# OpenBook.net
KiCad netlist of a schematic drawn in EAGLE
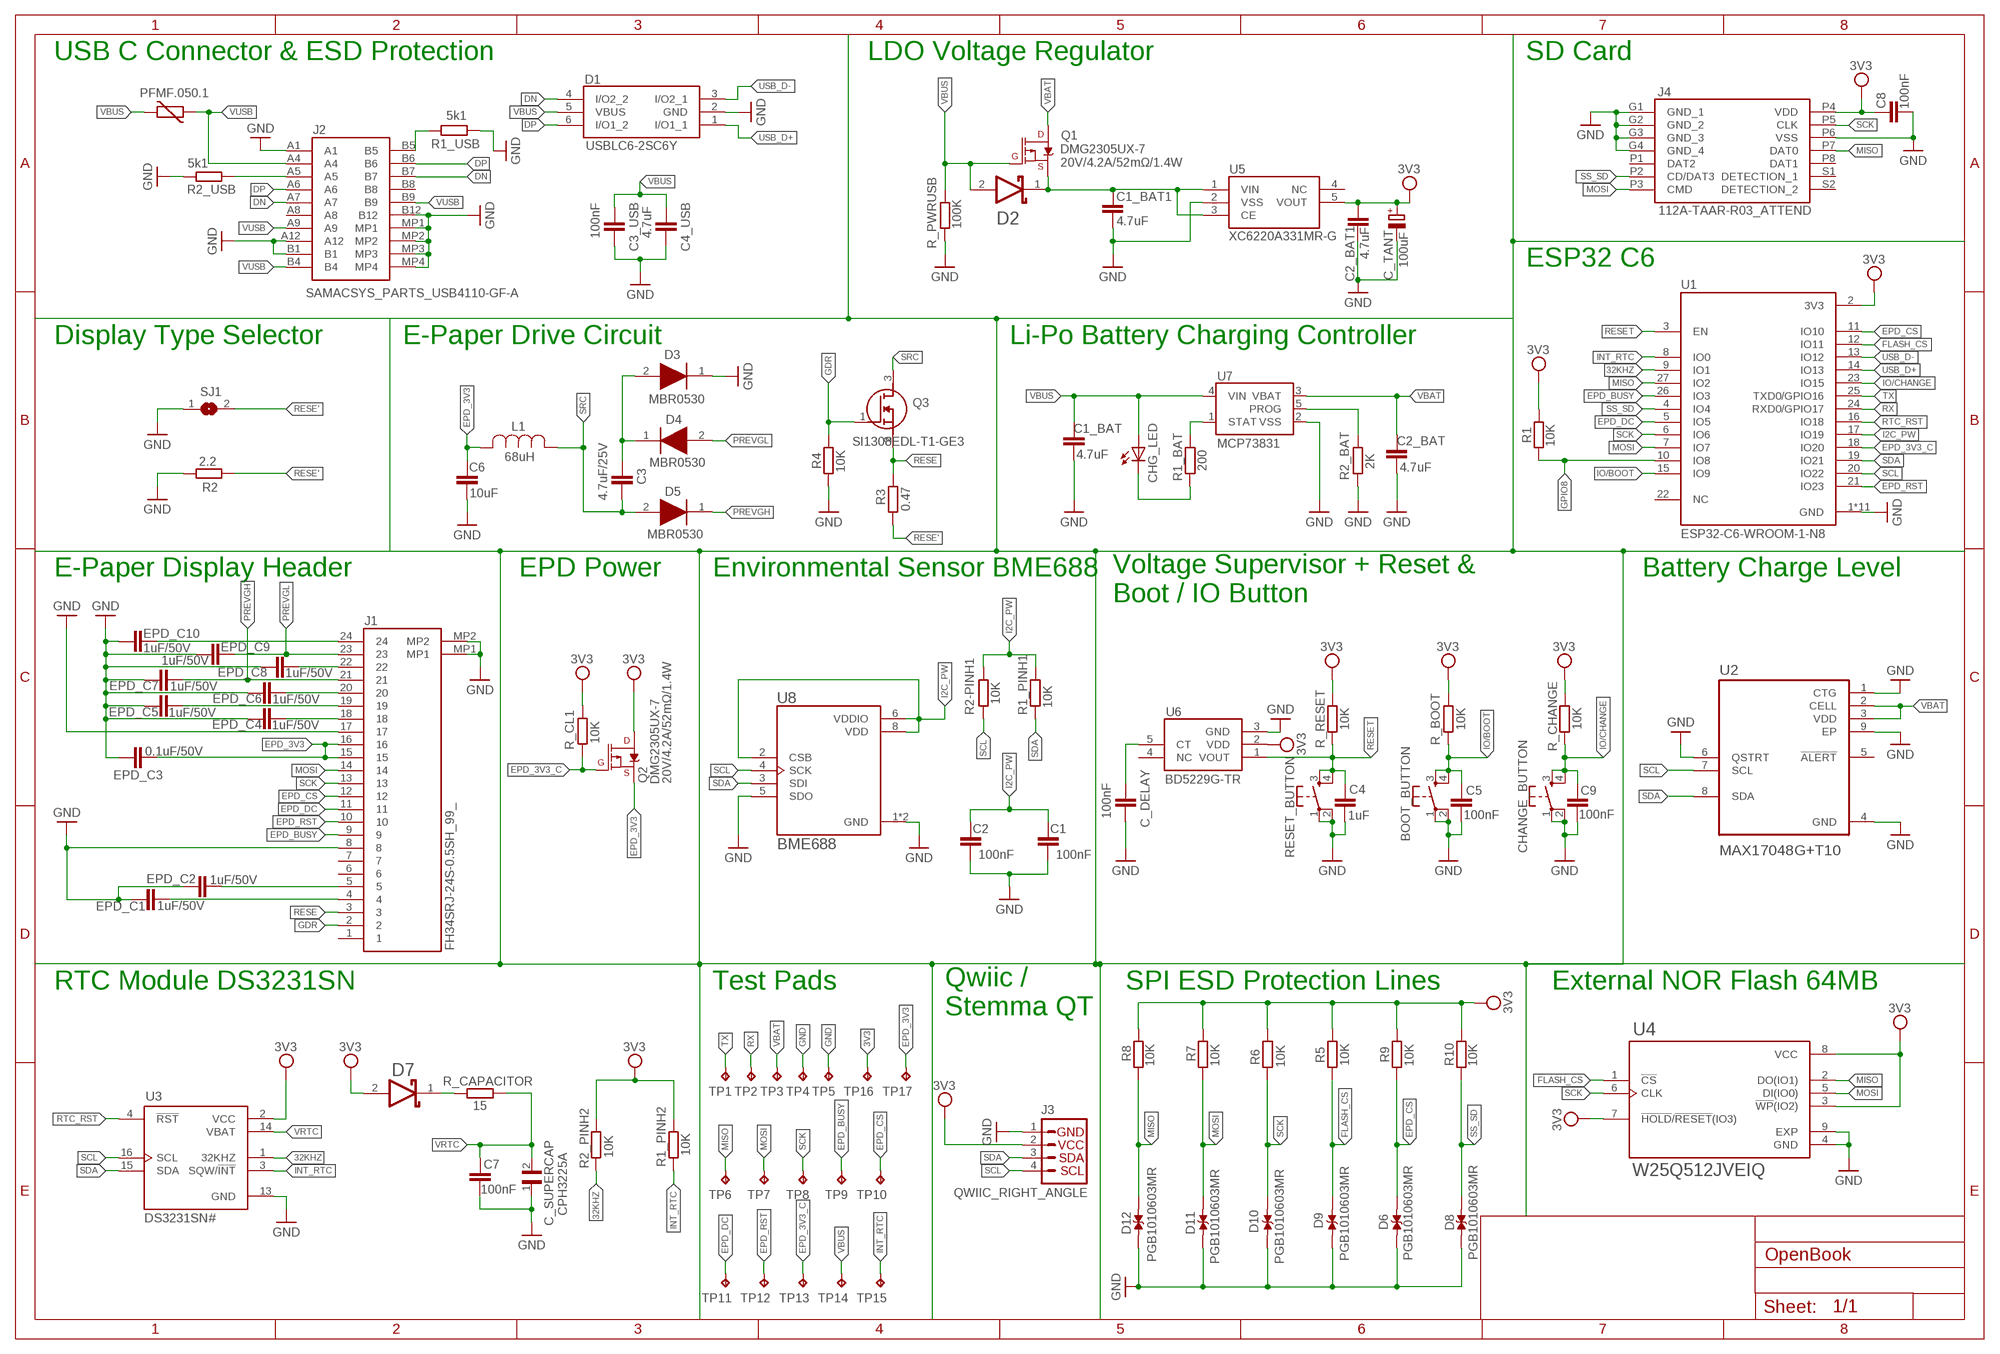
[diagram p0: schematic, sheet 1]

(export (version "E")
  (design (tool "Eeschema 10.0.6"))
  (components
    (comp (ref "BOOT_BUTTON")
      (value "BUTTON_CUSYOMV1")
      (footprint "eagle-import:MYBUTTON")
      (libsource (lib "eagle-import") (part "BUTTON_CUSYOMV1"))
    )
    (comp (ref "C1")
      (value "100nF")
      (footprint "eagle-import:EAGLE-LTSPICE_C0402")
      (libsource (lib "eagle-import") (part "ESP32_WROVER_EAGLE-LTSPICE_C0402"))
    )
    (comp (ref "C1_BAT")
      (value "4.7uF")
      (footprint "eagle-import:EAGLE-LTSPICE_C0402")
      (libsource (lib "eagle-import") (part "ESP32_WROVER_EAGLE-LTSPICE_C0402"))
    )
    (comp (ref "C1_BAT1")
      (value "4.7uF")
      (footprint "eagle-import:EAGLE-LTSPICE_C0402")
      (libsource (lib "eagle-import") (part "ESP32_WROVER_EAGLE-LTSPICE_C0402"))
    )
    (comp (ref "C2")
      (value "100nF")
      (footprint "eagle-import:EAGLE-LTSPICE_C0402")
      (libsource (lib "eagle-import") (part "ESP32_WROVER_EAGLE-LTSPICE_C0402"))
    )
    (comp (ref "C2_BAT")
      (value "4.7uF")
      (footprint "eagle-import:EAGLE-LTSPICE_C0402")
      (libsource (lib "eagle-import") (part "ESP32_WROVER_EAGLE-LTSPICE_C0402"))
    )
    (comp (ref "C2_BAT1")
      (value "4.7uF")
      (footprint "eagle-import:EAGLE-LTSPICE_C0402")
      (libsource (lib "eagle-import") (part "ESP32_WROVER_EAGLE-LTSPICE_C0402"))
    )
    (comp (ref "C3")
      (value "4.7uF/25V")
      (footprint "eagle-import:EAGLE-LTSPICE_C0402")
      (libsource (lib "eagle-import") (part "ESP32_WROVER_EAGLE-LTSPICE_C0402"))
    )
    (comp (ref "C3_USB")
      (value "100nF")
      (footprint "eagle-import:EAGLE-LTSPICE_C0402")
      (libsource (lib "eagle-import") (part "ESP32_WROVER_EAGLE-LTSPICE_C0402"))
    )
    (comp (ref "C4")
      (value "1uF")
      (footprint "eagle-import:EAGLE-LTSPICE_C0402")
      (libsource (lib "eagle-import") (part "ESP32_WROVER_EAGLE-LTSPICE_C0402"))
    )
    (comp (ref "C4_USB")
      (value "4.7uF")
      (footprint "eagle-import:EAGLE-LTSPICE_C0402")
      (libsource (lib "eagle-import") (part "ESP32_WROVER_EAGLE-LTSPICE_C0402"))
    )
    (comp (ref "C5")
      (value "100nF")
      (footprint "eagle-import:EAGLE-LTSPICE_C0402")
      (libsource (lib "eagle-import") (part "ESP32_WROVER_EAGLE-LTSPICE_C0402"))
    )
    (comp (ref "C6")
      (value "10uF")
      (footprint "eagle-import:EAGLE-LTSPICE_C0402")
      (libsource (lib "eagle-import") (part "ESP32_WROVER_EAGLE-LTSPICE_C0402"))
    )
    (comp (ref "C7")
      (value "100nF")
      (footprint "eagle-import:EAGLE-LTSPICE_C0402")
      (libsource (lib "eagle-import") (part "ESP32_WROVER_EAGLE-LTSPICE_C0402"))
    )
    (comp (ref "C8")
      (value "100nF")
      (footprint "eagle-import:EAGLE-LTSPICE_C0402")
      (libsource (lib "eagle-import") (part "ESP32_WROVER_EAGLE-LTSPICE_C0402"))
    )
    (comp (ref "C9")
      (value "100nF")
      (footprint "eagle-import:EAGLE-LTSPICE_C0402")
      (libsource (lib "eagle-import") (part "ESP32_WROVER_EAGLE-LTSPICE_C0402"))
    )
    (comp (ref "CHANGE_BUTTON")
      (value "BUTTON_CUSYOMV1")
      (footprint "eagle-import:MYBUTTON")
      (libsource (lib "eagle-import") (part "BUTTON_CUSYOMV1"))
    )
    (comp (ref "CHG_LED")
      (value "ADAFRUIT_LEDCHIP-LED0603")
      (footprint "eagle-import:ADAFRUIT_CHIP-LED0603")
      (libsource (lib "eagle-import") (part "ADAFRUIT_LEDCHIP-LED0603"))
    )
    (comp (ref "C_DELAY")
      (value "100nF")
      (footprint "eagle-import:EAGLE-LTSPICE_C0402")
      (libsource (lib "eagle-import") (part "ESP32_WROVER_EAGLE-LTSPICE_C0402"))
    )
    (comp (ref "C_SUPERCAP")
      (value "CPH3225A")
      (footprint "eagle-import:CAPCP3225X100N")
      (libsource (lib "eagle-import") (part "CPH3225A"))
    )
    (comp (ref "C_TANT")
      (value "100uF")
      (footprint "eagle-import:RCL_CT3528")
      (libsource (lib "eagle-import") (part "RCL_CPOL-EUCT3528"))
    )
    (comp (ref "D1")
      (value "USBLC6-2SC6Y")
      (footprint "eagle-import:SON50P200X200X80-9N")
      (fields (field (name "MF") "STMicroelectronics") (field (name "FF") "FF"))
      (libsource (lib "eagle-import") (part "USBLC6-2SC6Y"))
    )
    (comp (ref "D2")
      (value "ESP32_WROVER_AVX---SD0805S020S1R0_AVX_SD0805S020S1R0_0_0AVX_SD0805S020S1R0_0_0")
      (footprint "eagle-import:ESP32_WROVER_AVX---SD0805S020S1R0_AVX_SD0805S020S1R0_0")
      (libsource (lib "eagle-import") (part "ESP32_WROVER_AVX---SD0805S020S1R0_AVX_SD0805S020S1R0_0_0AVX_SD0805S020S1R0_0_0"))
    )
    (comp (ref "D3")
      (value "MBR0530")
      (footprint "eagle-import:SOD3716X135N")
      (fields (field (name "MF") "ON Semiconductor"))
      (libsource (lib "eagle-import") (part "MBR0530"))
    )
    (comp (ref "D4")
      (value "MBR0530")
      (footprint "eagle-import:SOD3716X135N")
      (fields (field (name "MF") "ON Semiconductor"))
      (libsource (lib "eagle-import") (part "MBR0530"))
    )
    (comp (ref "D5")
      (value "MBR0530")
      (footprint "eagle-import:SOD3716X135N")
      (fields (field (name "MF") "ON Semiconductor"))
      (libsource (lib "eagle-import") (part "MBR0530"))
    )
    (comp (ref "D6")
      (value "PGB1010603MR")
      (footprint "eagle-import:DIOC1608X36N")
      (fields (field (name "MF") "Littelfuse Inc."))
      (libsource (lib "eagle-import") (part "PGB1010603MR"))
    )
    (comp (ref "D7")
      (value "ESP32_WROVER_AVX---SD0805S020S1R0_AVX_SD0805S020S1R0_0_0AVX_SD0805S020S1R0_0_0")
      (footprint "eagle-import:ESP32_WROVER_AVX---SD0805S020S1R0_AVX_SD0805S020S1R0_0")
      (libsource (lib "eagle-import") (part "ESP32_WROVER_AVX---SD0805S020S1R0_AVX_SD0805S020S1R0_0_0AVX_SD0805S020S1R0_0_0"))
    )
    (comp (ref "D8")
      (value "PGB1010603MR")
      (footprint "eagle-import:DIOC1608X36N")
      (fields (field (name "MF") "Littelfuse Inc."))
      (libsource (lib "eagle-import") (part "PGB1010603MR"))
    )
    (comp (ref "D9")
      (value "PGB1010603MR")
      (footprint "eagle-import:DIOC1608X36N")
      (fields (field (name "MF") "Littelfuse Inc."))
      (libsource (lib "eagle-import") (part "PGB1010603MR"))
    )
    (comp (ref "D10")
      (value "PGB1010603MR")
      (footprint "eagle-import:DIOC1608X36N")
      (fields (field (name "MF") "Littelfuse Inc."))
      (libsource (lib "eagle-import") (part "PGB1010603MR"))
    )
    (comp (ref "D11")
      (value "PGB1010603MR")
      (footprint "eagle-import:DIOC1608X36N")
      (fields (field (name "MF") "Littelfuse Inc."))
      (libsource (lib "eagle-import") (part "PGB1010603MR"))
    )
    (comp (ref "D12")
      (value "PGB1010603MR")
      (footprint "eagle-import:DIOC1608X36N")
      (fields (field (name "MF") "Littelfuse Inc."))
      (libsource (lib "eagle-import") (part "PGB1010603MR"))
    )
    (comp (ref "EPD_C1")
      (value "1uF/50V")
      (footprint "eagle-import:EAGLE-LTSPICE_C0402")
      (libsource (lib "eagle-import") (part "ESP32_WROVER_EAGLE-LTSPICE_C0402"))
    )
    (comp (ref "EPD_C2")
      (value "1uF/50V")
      (footprint "eagle-import:EAGLE-LTSPICE_C0402")
      (libsource (lib "eagle-import") (part "ESP32_WROVER_EAGLE-LTSPICE_C0402"))
    )
    (comp (ref "EPD_C3")
      (value "0.1uF/50V")
      (footprint "eagle-import:EAGLE-LTSPICE_C0402")
      (libsource (lib "eagle-import") (part "ESP32_WROVER_EAGLE-LTSPICE_C0402"))
    )
    (comp (ref "EPD_C4")
      (value "1uF/50V")
      (footprint "eagle-import:EAGLE-LTSPICE_C0402")
      (libsource (lib "eagle-import") (part "ESP32_WROVER_EAGLE-LTSPICE_C0402"))
    )
    (comp (ref "EPD_C5")
      (value "1uF/50V")
      (footprint "eagle-import:EAGLE-LTSPICE_C0402")
      (libsource (lib "eagle-import") (part "ESP32_WROVER_EAGLE-LTSPICE_C0402"))
    )
    (comp (ref "EPD_C6")
      (value "1uF/50V")
      (footprint "eagle-import:EAGLE-LTSPICE_C0402")
      (libsource (lib "eagle-import") (part "ESP32_WROVER_EAGLE-LTSPICE_C0402"))
    )
    (comp (ref "EPD_C7")
      (value "1uF/50V")
      (footprint "eagle-import:EAGLE-LTSPICE_C0402")
      (libsource (lib "eagle-import") (part "ESP32_WROVER_EAGLE-LTSPICE_C0402"))
    )
    (comp (ref "EPD_C8")
      (value "1uF/50V")
      (footprint "eagle-import:EAGLE-LTSPICE_C0402")
      (libsource (lib "eagle-import") (part "ESP32_WROVER_EAGLE-LTSPICE_C0402"))
    )
    (comp (ref "EPD_C9")
      (value "1uF/50V")
      (footprint "eagle-import:EAGLE-LTSPICE_C0402")
      (libsource (lib "eagle-import") (part "ESP32_WROVER_EAGLE-LTSPICE_C0402"))
    )
    (comp (ref "EPD_C10")
      (value "1uF/50V")
      (footprint "eagle-import:EAGLE-LTSPICE_C0402")
      (libsource (lib "eagle-import") (part "ESP32_WROVER_EAGLE-LTSPICE_C0402"))
    )
    (comp (ref "J1")
      (value "FH34SRJ-24S-0.5SH_99_")
      (footprint "eagle-import:FH34SRJ24S05SH99")
      (fields
        (field (name "MANUFACTURER_PART_NUMBER") "FH34SRJ-24S-0.5SH(99)")
        (field (name "MOUSER_PART_NUMBER") "798-FH34SRJ24S05SH99")
      )
      (libsource (lib "eagle-import") (part "FH34SRJ-24S-0.5SH_99_"))
    )
    (comp (ref "J2")
      (value "SAMACSYS_PARTS_USB4110-GF-A")
      (footprint "eagle-import:SAMACSYS_PARTS_USB4110GFA")
      (fields
        (field (name "MANUFACTURER_PART_NUMBER") "USB4110-GF-A")
        (field (name "MOUSER_PART_NUMBER") "640-USB4110-GF-A")
      )
      (libsource (lib "eagle-import") (part "SAMACSYS_PARTS_USB4110-GF-A"))
    )
    (comp (ref "J3")
      (value "QWIIC_RIGHT_ANGLE")
      (footprint "eagle-import:JST04_1MM_RA")
      (libsource (lib "eagle-import") (part "QWIIC_CONNECTORJS-1MM"))
    )
    (comp (ref "J4")
      (value "112A-TAAR-R03_ATTEND")
      (footprint "eagle-import:112ATAARR03ATTEND")
      (libsource (lib "eagle-import") (part "112A-TAAR-R03_ATTEND"))
    )
    (comp (ref "L1")
      (value "68uH")
      (footprint "eagle-import:IND_4828-WE-TPC_WRE")
      (libsource (lib "eagle-import") (part "744043680IND_4828-WE-TPC_WRE"))
    )
    (comp (ref "PFMF.050.1")
      (value "ESP32C6_VARISTORCN1812")
      (footprint "eagle-import:ESP32C6_VARISTOR_CT_CN1812")
      (libsource (lib "eagle-import") (part "ESP32C6_VARISTORCN1812"))
    )
    (comp (ref "Q1")
      (value "20V/4.2A/52mΩ/1.4W")
      (footprint "eagle-import:ESP32_WROVER_SPARKFUN-DISCRETESEMI_SOT23-3")
      (fields (field (name "PROD_ID") "TRAN-14388") (field (name "PROD_ID_1") "DMG2305UX-7"))
      (libsource (lib "eagle-import") (part "ESP32_WROVER_SPARKFUN-DISCRETESEMI_MOSFET_PCH-DMG2305UX-7"))
    )
    (comp (ref "Q2")
      (value "20V/4.2A/52mΩ/1.4W")
      (footprint "eagle-import:ESP32_WROVER_SPARKFUN-DISCRETESEMI_SOT23-3")
      (fields (field (name "PROD_ID") "TRAN-14388") (field (name "PROD_ID_1") "DMG2305UX-7"))
      (libsource (lib "eagle-import") (part "ESP32_WROVER_SPARKFUN-DISCRETESEMI_MOSFET_PCH-DMG2305UX-7"))
    )
    (comp (ref "Q3")
      (value "SI1308EDL-T1-GE3")
      (footprint "eagle-import:SOT65P210X110-3N")
      (fields (field (name "MF") "Vishay Siliconix"))
      (libsource (lib "eagle-import") (part "SI1308EDL-T1-GE3"))
    )
    (comp (ref "R1")
      (value "10K")
      (footprint "eagle-import:ESP32_WROVER_EAGLE-LTSPICE_R0402")
      (libsource (lib "eagle-import") (part "ESP32_WROVER_EAGLE-LTSPICE_RR0402"))
    )
    (comp (ref "R1_BAT")
      (value "200")
      (footprint "eagle-import:ESP32_WROVER_EAGLE-LTSPICE_R0402")
      (libsource (lib "eagle-import") (part "ESP32_WROVER_EAGLE-LTSPICE_RR0402"))
    )
    (comp (ref "R1_PINH1")
      (value "10K")
      (footprint "eagle-import:ESP32_WROVER_EAGLE-LTSPICE_R0402")
      (libsource (lib "eagle-import") (part "ESP32_WROVER_EAGLE-LTSPICE_RR0402"))
    )
    (comp (ref "R1_PINH2")
      (value "10K")
      (footprint "eagle-import:ESP32_WROVER_EAGLE-LTSPICE_R0402")
      (libsource (lib "eagle-import") (part "ESP32_WROVER_EAGLE-LTSPICE_RR0402"))
    )
    (comp (ref "R1_USB")
      (value "5k1")
      (footprint "eagle-import:ESP32_WROVER_EAGLE-LTSPICE_R0402")
      (libsource (lib "eagle-import") (part "ESP32_WROVER_EAGLE-LTSPICE_RR0402"))
    )
    (comp (ref "R2")
      (value "2.2")
      (footprint "eagle-import:ESP32_WROVER_EAGLE-LTSPICE_R0402")
      (libsource (lib "eagle-import") (part "ESP32_WROVER_EAGLE-LTSPICE_RR0402"))
    )
    (comp (ref "R2-PINH1")
      (value "10K")
      (footprint "eagle-import:ESP32_WROVER_EAGLE-LTSPICE_R0402")
      (libsource (lib "eagle-import") (part "ESP32_WROVER_EAGLE-LTSPICE_RR0402"))
    )
    (comp (ref "R2_BAT")
      (value "2K")
      (footprint "eagle-import:ESP32_WROVER_EAGLE-LTSPICE_R0402")
      (libsource (lib "eagle-import") (part "ESP32_WROVER_EAGLE-LTSPICE_RR0402"))
    )
    (comp (ref "R2_PINH2")
      (value "10K")
      (footprint "eagle-import:ESP32_WROVER_EAGLE-LTSPICE_R0402")
      (libsource (lib "eagle-import") (part "ESP32_WROVER_EAGLE-LTSPICE_RR0402"))
    )
    (comp (ref "R2_USB")
      (value "5k1")
      (footprint "eagle-import:ESP32_WROVER_EAGLE-LTSPICE_R0402")
      (libsource (lib "eagle-import") (part "ESP32_WROVER_EAGLE-LTSPICE_RR0402"))
    )
    (comp (ref "R3")
      (value "0.47")
      (footprint "eagle-import:ESP32_WROVER_EAGLE-LTSPICE_R0402")
      (libsource (lib "eagle-import") (part "ESP32_WROVER_EAGLE-LTSPICE_RR0402"))
    )
    (comp (ref "R4")
      (value "10K")
      (footprint "eagle-import:ESP32_WROVER_EAGLE-LTSPICE_R0402")
      (libsource (lib "eagle-import") (part "ESP32_WROVER_EAGLE-LTSPICE_RR0402"))
    )
    (comp (ref "R5")
      (value "10K")
      (footprint "eagle-import:ESP32_WROVER_EAGLE-LTSPICE_R0402")
      (libsource (lib "eagle-import") (part "ESP32_WROVER_EAGLE-LTSPICE_RR0402"))
    )
    (comp (ref "R6")
      (value "10K")
      (footprint "eagle-import:ESP32_WROVER_EAGLE-LTSPICE_R0402")
      (libsource (lib "eagle-import") (part "ESP32_WROVER_EAGLE-LTSPICE_RR0402"))
    )
    (comp (ref "R7")
      (value "10K")
      (footprint "eagle-import:ESP32_WROVER_EAGLE-LTSPICE_R0402")
      (libsource (lib "eagle-import") (part "ESP32_WROVER_EAGLE-LTSPICE_RR0402"))
    )
    (comp (ref "R8")
      (value "10K")
      (footprint "eagle-import:ESP32_WROVER_EAGLE-LTSPICE_R0402")
      (libsource (lib "eagle-import") (part "ESP32_WROVER_EAGLE-LTSPICE_RR0402"))
    )
    (comp (ref "R9")
      (value "10K")
      (footprint "eagle-import:ESP32_WROVER_EAGLE-LTSPICE_R0402")
      (libsource (lib "eagle-import") (part "ESP32_WROVER_EAGLE-LTSPICE_RR0402"))
    )
    (comp (ref "R10")
      (value "10K")
      (footprint "eagle-import:ESP32_WROVER_EAGLE-LTSPICE_R0402")
      (libsource (lib "eagle-import") (part "ESP32_WROVER_EAGLE-LTSPICE_RR0402"))
    )
    (comp (ref "RESET_BUTTON")
      (value "BUTTON_CUSYOMV1")
      (footprint "eagle-import:MYBUTTON")
      (libsource (lib "eagle-import") (part "BUTTON_CUSYOMV1"))
    )
    (comp (ref "R_BOOT")
      (value "10K")
      (footprint "eagle-import:ESP32_WROVER_EAGLE-LTSPICE_R0402")
      (libsource (lib "eagle-import") (part "ESP32_WROVER_EAGLE-LTSPICE_RR0402"))
    )
    (comp (ref "R_CAPACITOR")
      (value "15")
      (footprint "eagle-import:ESP32_WROVER_EAGLE-LTSPICE_R0402")
      (libsource (lib "eagle-import") (part "ESP32_WROVER_EAGLE-LTSPICE_RR0402"))
    )
    (comp (ref "R_CHANGE")
      (value "10K")
      (footprint "eagle-import:ESP32_WROVER_EAGLE-LTSPICE_R0402")
      (libsource (lib "eagle-import") (part "ESP32_WROVER_EAGLE-LTSPICE_RR0402"))
    )
    (comp (ref "R_CL1")
      (value "10K")
      (footprint "eagle-import:ESP32_WROVER_EAGLE-LTSPICE_R0402")
      (libsource (lib "eagle-import") (part "ESP32_WROVER_EAGLE-LTSPICE_RR0402"))
    )
    (comp (ref "R_PWRUSB")
      (value "100K")
      (footprint "eagle-import:ESP32_WROVER_EAGLE-LTSPICE_R0402")
      (libsource (lib "eagle-import") (part "ESP32_WROVER_EAGLE-LTSPICE_RR0402"))
    )
    (comp (ref "R_RESET")
      (value "10K")
      (footprint "eagle-import:ESP32_WROVER_EAGLE-LTSPICE_R0402")
      (libsource (lib "eagle-import") (part "ESP32_WROVER_EAGLE-LTSPICE_RR0402"))
    )
    (comp (ref "SJ1") (value "SJ") (footprint "eagle-import:SJ") (libsource (lib "eagle-import") (part "SJ")))
    (comp (ref "TP1")
      (value "TPTP20R")
      (footprint "eagle-import:TP20R")
      (fields (field (name "TP_SIGNAL_NAME") "TX"))
      (libsource (lib "eagle-import") (part "TPTP20R"))
    )
    (comp (ref "TP2")
      (value "TPTP20R")
      (footprint "eagle-import:TP20R")
      (fields (field (name "TP_SIGNAL_NAME") "RX"))
      (libsource (lib "eagle-import") (part "TPTP20R"))
    )
    (comp (ref "TP3")
      (value "TPTP20R")
      (footprint "eagle-import:TP20R")
      (fields (field (name "TP_SIGNAL_NAME") "VBAT"))
      (libsource (lib "eagle-import") (part "TPTP20R"))
    )
    (comp (ref "TP4")
      (value "TPTP20R")
      (footprint "eagle-import:TP20R")
      (fields (field (name "TP_SIGNAL_NAME") "GND"))
      (libsource (lib "eagle-import") (part "TPTP20R"))
    )
    (comp (ref "TP5")
      (value "TPTP20R")
      (footprint "eagle-import:TP20R")
      (fields (field (name "TP_SIGNAL_NAME") "GND"))
      (libsource (lib "eagle-import") (part "TPTP20R"))
    )
    (comp (ref "TP6")
      (value "TPTP20R")
      (footprint "eagle-import:TP20R")
      (fields (field (name "TP_SIGNAL_NAME") "MISO"))
      (libsource (lib "eagle-import") (part "TPTP20R"))
    )
    (comp (ref "TP7")
      (value "TPTP20R")
      (footprint "eagle-import:TP20R")
      (fields (field (name "TP_SIGNAL_NAME") "MOSI"))
      (libsource (lib "eagle-import") (part "TPTP20R"))
    )
    (comp (ref "TP8")
      (value "TPTP20R")
      (footprint "eagle-import:TP20R")
      (fields (field (name "TP_SIGNAL_NAME") "SCK"))
      (libsource (lib "eagle-import") (part "TPTP20R"))
    )
    (comp (ref "TP9")
      (value "TPTP20R")
      (footprint "eagle-import:TP20R")
      (fields (field (name "TP_SIGNAL_NAME") "EPD_BUSY"))
      (libsource (lib "eagle-import") (part "TPTP20R"))
    )
    (comp (ref "TP10")
      (value "TPTP20R")
      (footprint "eagle-import:TP20R")
      (fields (field (name "TP_SIGNAL_NAME") "EPD_CS"))
      (libsource (lib "eagle-import") (part "TPTP20R"))
    )
    (comp (ref "TP11")
      (value "TPTP20R")
      (footprint "eagle-import:TP20R")
      (fields (field (name "TP_SIGNAL_NAME") "EPD_DC"))
      (libsource (lib "eagle-import") (part "TPTP20R"))
    )
    (comp (ref "TP12")
      (value "TPTP20R")
      (footprint "eagle-import:TP20R")
      (fields (field (name "TP_SIGNAL_NAME") "EPD_RST"))
      (libsource (lib "eagle-import") (part "TPTP20R"))
    )
    (comp (ref "TP13")
      (value "TPTP20R")
      (footprint "eagle-import:TP20R")
      (fields (field (name "TP_SIGNAL_NAME") "EPD_3V3_c"))
      (libsource (lib "eagle-import") (part "TPTP20R"))
    )
    (comp (ref "TP14")
      (value "TPTP20R")
      (footprint "eagle-import:TP20R")
      (fields (field (name "TP_SIGNAL_NAME") "VBUS"))
      (libsource (lib "eagle-import") (part "TPTP20R"))
    )
    (comp (ref "TP15")
      (value "TPTP20R")
      (footprint "eagle-import:TP20R")
      (fields (field (name "TP_SIGNAL_NAME") "INT_RTC"))
      (libsource (lib "eagle-import") (part "TPTP20R"))
    )
    (comp (ref "TP16")
      (value "TPTP20R")
      (footprint "eagle-import:TP20R")
      (fields (field (name "TP_SIGNAL_NAME") "3V3"))
      (libsource (lib "eagle-import") (part "TPTP20R"))
    )
    (comp (ref "TP17")
      (value "TPTP20R")
      (footprint "eagle-import:TP20R")
      (fields (field (name "TP_SIGNAL_NAME") "EPD_3V3"))
      (libsource (lib "eagle-import") (part "TPTP20R"))
    )
    (comp (ref "U1")
      (value "ESP32-C6-WROOM-1-N8")
      (footprint "eagle-import:XCVR_ESP32-C6-WROOM-1-N8")
      (libsource (lib "eagle-import") (part "ESP32-C6-WROOM-1-N8"))
    )
    (comp (ref "U2")
      (value "MAX17048G+T10")
      (footprint "eagle-import:SON50P200X200X80-9N")
      (fields (field (name "MF") "Analog Devices"))
      (libsource (lib "eagle-import") (part "MAX17048G+T10"))
    )
    (comp (ref "U3")
      (value "DS3231SN#")
      (footprint "eagle-import:SOIC127P1032X265-16N")
      (libsource (lib "eagle-import") (part "DS3231SN#"))
    )
    (comp (ref "U4")
      (value "W25Q512JVEIQ")
      (footprint "eagle-import:SON127P600X800X80-9N")
      (fields (field (name "MF") "Winbond Electronics"))
      (libsource (lib "eagle-import") (part "W25Q512JVEIQ"))
    )
    (comp (ref "U5")
      (value "XC6220A331MR-G")
      (footprint "eagle-import:SOT95P280X120-5N")
      (fields (field (name "MOUSER_PART_NUMBER") "865-XC6220A331MR-G"))
      (libsource (lib "eagle-import") (part "XC6220A331MR-G"))
    )
    (comp (ref "U6")
      (value "BD5229G-TR")
      (footprint "eagle-import:SOT95P280X125-5N")
      (libsource (lib "eagle-import") (part "BD5229G-TR"))
    )
    (comp (ref "U7")
      (value "MCP73831")
      (footprint "eagle-import:ESP32_WROVER_SPARKFUN-IC-POWER_SOT23-5")
      (libsource (lib "eagle-import") (part "ESP32_WROVER_SPARKFUN-IC-POWER_MCP73831"))
    )
    (comp (ref "U8")
      (value "BME688")
      (footprint "eagle-import:ESP32_WROVER_BME680_PSON80P300X300X100-8N")
      (fields (field (name "MF") "Bosch Sensortec") (field (name "MP") "BME680"))
      (libsource (lib "eagle-import") (part "ESP32_WROVER_BME680_BME680"))
    )
  )
  (nets
    (net (code "1") (name "3V3") (class "Default")
      (node (ref "C2_BAT1") (pin "1") (pinfunction "1_1") (pintype "passive"))
      (node (ref "C8") (pin "1") (pinfunction "1_1") (pintype "passive"))
      (node (ref "C_TANT") (pin "+") (pinfunction "+_+") (pintype "passive"))
      (node (ref "D7") (pin "2") (pinfunction "ANODE_2") (pintype "bidirectional"))
      (node (ref "J3") (pin "2") (pinfunction "2_2") (pintype "power_in"))
      (node (ref "J4") (pin "P4") (pinfunction "VDD_P4") (pintype "bidirectional"))
      (node (ref "Q2") (pin "3") (pinfunction "D_3") (pintype "bidirectional"))
      (node (ref "R1") (pin "2") (pinfunction "2_2") (pintype "passive"))
      (node (ref "R10") (pin "2") (pinfunction "2_2") (pintype "passive"))
      (node (ref "R1_PINH2") (pin "2") (pinfunction "2_2") (pintype "passive"))
      (node (ref "R2_PINH2") (pin "2") (pinfunction "2_2") (pintype "passive"))
      (node (ref "R5") (pin "2") (pinfunction "2_2") (pintype "passive"))
      (node (ref "R6") (pin "2") (pinfunction "2_2") (pintype "passive"))
      (node (ref "R7") (pin "2") (pinfunction "2_2") (pintype "passive"))
      (node (ref "R8") (pin "2") (pinfunction "2_2") (pintype "passive"))
      (node (ref "R9") (pin "2") (pinfunction "2_2") (pintype "passive"))
      (node (ref "R_BOOT") (pin "2") (pinfunction "2_2") (pintype "passive"))
      (node (ref "R_CHANGE") (pin "2") (pinfunction "2_2") (pintype "passive"))
      (node (ref "R_CL1") (pin "2") (pinfunction "2_2") (pintype "passive"))
      (node (ref "R_RESET") (pin "2") (pinfunction "2_2") (pintype "passive"))
      (node (ref "TP16") (pin "TP") (pinfunction "TP_TP") (pintype "input"))
      (node (ref "U1") (pin "2") (pinfunction "3V3_2") (pintype "power_in"))
      (node (ref "U3") (pin "2") (pinfunction "VCC_2") (pintype "power_in"))
      (node (ref "U4") (pin "3") (pinfunction "~{WP}(IO2)_3") (pintype "bidirectional"))
      (node (ref "U4") (pin "7") (pinfunction "~{HOLD}/~{RESET}(IO3)_7") (pintype "bidirectional"))
      (node (ref "U4") (pin "8") (pinfunction "VCC_8") (pintype "power_in"))
      (node (ref "U5") (pin "5") (pinfunction "VOUT_5") (pintype "bidirectional"))
      (node (ref "U6") (pin "2") (pinfunction "VDD_2") (pintype "bidirectional"))
    )
    (net (code "2") (name "32KHZ") (class "Default")
      (node (ref "R2_PINH2") (pin "1") (pinfunction "1_1") (pintype "passive"))
      (node (ref "U1") (pin "9") (pinfunction "IO1_9") (pintype "bidirectional"))
      (node (ref "U3") (pin "1") (pinfunction "32KHZ_1") (pintype "output"))
    )
    (net (code "3") (name "DN") (class "Default")
      (node (ref "D1") (pin "4") (pinfunction "I/O2_2_4") (pintype "bidirectional"))
      (node (ref "J2") (pin "A7") (pinfunction "A7_A7") (pintype "bidirectional"))
      (node (ref "J2") (pin "B7") (pinfunction "B7_B7") (pintype "bidirectional"))
    )
    (net (code "4") (name "DP") (class "Default")
      (node (ref "D1") (pin "6") (pinfunction "I/O1_2_6") (pintype "bidirectional"))
      (node (ref "J2") (pin "A6") (pinfunction "A6_A6") (pintype "bidirectional"))
      (node (ref "J2") (pin "B6") (pinfunction "B6_B6") (pintype "bidirectional"))
    )
    (net (code "5") (name "EPD_3V3") (class "Default")
      (node (ref "C6") (pin "1") (pinfunction "1_1") (pintype "passive"))
      (node (ref "EPD_C3") (pin "2") (pinfunction "2_2") (pintype "passive"))
      (node (ref "J1") (pin "15") (pinfunction "15_15") (pintype "bidirectional"))
      (node (ref "J1") (pin "16") (pinfunction "16_16") (pintype "bidirectional"))
      (node (ref "L1") (pin "2") (pinfunction "2_2") (pintype "passive"))
      (node (ref "Q2") (pin "2") (pinfunction "S_2") (pintype "bidirectional"))
      (node (ref "TP17") (pin "TP") (pinfunction "TP_TP") (pintype "input"))
    )
    (net (code "6") (name "EPD_3V3_C") (class "Default")
      (node (ref "Q2") (pin "1") (pinfunction "G_1") (pintype "bidirectional"))
      (node (ref "R_CL1") (pin "1") (pinfunction "1_1") (pintype "passive"))
      (node (ref "TP13") (pin "TP") (pinfunction "TP_TP") (pintype "input"))
      (node (ref "U1") (pin "18") (pinfunction "IO20_18") (pintype "bidirectional"))
    )
    (net (code "7") (name "EPD_BUSY") (class "Default")
      (node (ref "J1") (pin "9") (pinfunction "9_9") (pintype "bidirectional"))
      (node (ref "TP9") (pin "TP") (pinfunction "TP_TP") (pintype "input"))
      (node (ref "U1") (pin "26") (pinfunction "IO3_26") (pintype "bidirectional"))
    )
    (net (code "8") (name "EPD_CS") (class "Default")
      (node (ref "D6") (pin "2") (pinfunction "2_2") (pintype "passive"))
      (node (ref "J1") (pin "12") (pinfunction "12_12") (pintype "bidirectional"))
      (node (ref "R9") (pin "1") (pinfunction "1_1") (pintype "passive"))
      (node (ref "TP10") (pin "TP") (pinfunction "TP_TP") (pintype "input"))
      (node (ref "U1") (pin "11") (pinfunction "IO10_11") (pintype "bidirectional"))
    )
    (net (code "9") (name "EPD_DC") (class "Default")
      (node (ref "J1") (pin "11") (pinfunction "11_11") (pintype "bidirectional"))
      (node (ref "TP11") (pin "TP") (pinfunction "TP_TP") (pintype "input"))
      (node (ref "U1") (pin "5") (pinfunction "IO5_5") (pintype "bidirectional"))
    )
    (net (code "10") (name "EPD_RST") (class "Default")
      (node (ref "J1") (pin "10") (pinfunction "10_10") (pintype "bidirectional"))
      (node (ref "TP12") (pin "TP") (pinfunction "TP_TP") (pintype "input"))
      (node (ref "U1") (pin "21") (pinfunction "IO23_21") (pintype "bidirectional"))
    )
    (net (code "11") (name "FLASH_CS") (class "Default")
      (node (ref "D9") (pin "2") (pinfunction "2_2") (pintype "passive"))
      (node (ref "R5") (pin "1") (pinfunction "1_1") (pintype "passive"))
      (node (ref "U1") (pin "12") (pinfunction "IO11_12") (pintype "bidirectional"))
      (node (ref "U4") (pin "1") (pinfunction "~{CS}_1") (pintype "input"))
    )
    (net (code "12") (name "GDR") (class "Default")
      (node (ref "J1") (pin "2") (pinfunction "2_2") (pintype "bidirectional"))
      (node (ref "Q3") (pin "1") (pinfunction "G_1") (pintype "bidirectional"))
      (node (ref "R4") (pin "2") (pinfunction "2_2") (pintype "passive"))
    )
    (net (code "13") (name "GND") (class "Default")
      (node (ref "BOOT_BUTTON") (pin "1") (pinfunction "1_1") (pintype "passive"))
      (node (ref "BOOT_BUTTON") (pin "2") (pinfunction "2_2") (pintype "passive"))
      (node (ref "C1") (pin "2") (pinfunction "2_2") (pintype "passive"))
      (node (ref "C1_BAT") (pin "2") (pinfunction "2_2") (pintype "passive"))
      (node (ref "C1_BAT1") (pin "2") (pinfunction "2_2") (pintype "passive"))
      (node (ref "C2") (pin "2") (pinfunction "2_2") (pintype "passive"))
      (node (ref "C2_BAT") (pin "2") (pinfunction "2_2") (pintype "passive"))
      (node (ref "C2_BAT1") (pin "2") (pinfunction "2_2") (pintype "passive"))
      (node (ref "C3_USB") (pin "2") (pinfunction "2_2") (pintype "passive"))
      (node (ref "C4") (pin "2") (pinfunction "2_2") (pintype "passive"))
      (node (ref "C4_USB") (pin "2") (pinfunction "2_2") (pintype "passive"))
      (node (ref "C5") (pin "2") (pinfunction "2_2") (pintype "passive"))
      (node (ref "C6") (pin "2") (pinfunction "2_2") (pintype "passive"))
      (node (ref "C7") (pin "2") (pinfunction "2_2") (pintype "passive"))
      (node (ref "C8") (pin "2") (pinfunction "2_2") (pintype "passive"))
      (node (ref "C9") (pin "2") (pinfunction "2_2") (pintype "passive"))
      (node (ref "CHANGE_BUTTON") (pin "1") (pinfunction "1_1") (pintype "passive"))
      (node (ref "CHANGE_BUTTON") (pin "2") (pinfunction "2_2") (pintype "passive"))
      (node (ref "C_DELAY") (pin "2") (pinfunction "2_2") (pintype "passive"))
      (node (ref "C_SUPERCAP") (pin "1") (pinfunction "1_1") (pintype "passive"))
      (node (ref "C_TANT") (pin "-") (pinfunction "-_-") (pintype "passive"))
      (node (ref "D1") (pin "2") (pinfunction "GND_2") (pintype "bidirectional"))
      (node (ref "D10") (pin "1") (pinfunction "1_1") (pintype "passive"))
      (node (ref "D11") (pin "1") (pinfunction "1_1") (pintype "passive"))
      (node (ref "D12") (pin "1") (pinfunction "1_1") (pintype "passive"))
      (node (ref "D3") (pin "1") (pinfunction "K_1") (pintype "bidirectional"))
      (node (ref "D6") (pin "1") (pinfunction "1_1") (pintype "passive"))
      (node (ref "D8") (pin "1") (pinfunction "1_1") (pintype "passive"))
      (node (ref "D9") (pin "1") (pinfunction "1_1") (pintype "passive"))
      (node (ref "EPD_C1") (pin "1") (pinfunction "1_1") (pintype "passive"))
      (node (ref "EPD_C10") (pin "1") (pinfunction "1_1") (pintype "passive"))
      (node (ref "EPD_C2") (pin "1") (pinfunction "1_1") (pintype "passive"))
      (node (ref "EPD_C3") (pin "1") (pinfunction "1_1") (pintype "passive"))
      (node (ref "EPD_C4") (pin "1") (pinfunction "1_1") (pintype "passive"))
      (node (ref "EPD_C5") (pin "1") (pinfunction "1_1") (pintype "passive"))
      (node (ref "EPD_C6") (pin "1") (pinfunction "1_1") (pintype "passive"))
      (node (ref "EPD_C7") (pin "1") (pinfunction "1_1") (pintype "passive"))
      (node (ref "EPD_C8") (pin "1") (pinfunction "1_1") (pintype "passive"))
      (node (ref "EPD_C9") (pin "1") (pinfunction "1_1") (pintype "passive"))
      (node (ref "J1") (pin "17") (pinfunction "17_17") (pintype "bidirectional"))
      (node (ref "J1") (pin "8") (pinfunction "8_8") (pintype "bidirectional"))
      (node (ref "J1") (pin "MP1") (pinfunction "MP1_MP1") (pintype "bidirectional"))
      (node (ref "J1") (pin "MP2") (pinfunction "MP2_MP2") (pintype "bidirectional"))
      (node (ref "J2") (pin "A1") (pinfunction "A1_A1") (pintype "bidirectional"))
      (node (ref "J2") (pin "A12") (pinfunction "A12_A12") (pintype "bidirectional"))
      (node (ref "J2") (pin "B1") (pinfunction "B1_B1") (pintype "bidirectional"))
      (node (ref "J2") (pin "B12") (pinfunction "B12_B12") (pintype "bidirectional"))
      (node (ref "J2") (pin "MP1") (pinfunction "MP1_MP1") (pintype "bidirectional"))
      (node (ref "J2") (pin "MP2") (pinfunction "MP2_MP2") (pintype "bidirectional"))
      (node (ref "J2") (pin "MP3") (pinfunction "MP3_MP3") (pintype "bidirectional"))
      (node (ref "J2") (pin "MP4") (pinfunction "MP4_MP4") (pintype "bidirectional"))
      (node (ref "J3") (pin "1") (pinfunction "1_1") (pintype "power_in"))
      (node (ref "J4") (pin "G1") (pinfunction "GND_1_G1") (pintype "bidirectional"))
      (node (ref "J4") (pin "G2") (pinfunction "GND_2_G2") (pintype "bidirectional"))
      (node (ref "J4") (pin "G3") (pinfunction "GND_3_G3") (pintype "bidirectional"))
      (node (ref "J4") (pin "G4") (pinfunction "GND_4_G4") (pintype "bidirectional"))
      (node (ref "J4") (pin "P6") (pinfunction "VSS_P6") (pintype "bidirectional"))
      (node (ref "R1_USB") (pin "2") (pinfunction "2_2") (pintype "passive"))
      (node (ref "R2") (pin "2") (pinfunction "2_2") (pintype "passive"))
      (node (ref "R2_BAT") (pin "1") (pinfunction "1_1") (pintype "passive"))
      (node (ref "R2_USB") (pin "1") (pinfunction "1_1") (pintype "passive"))
      (node (ref "R4") (pin "1") (pinfunction "1_1") (pintype "passive"))
      (node (ref "RESET_BUTTON") (pin "1") (pinfunction "1_1") (pintype "passive"))
      (node (ref "RESET_BUTTON") (pin "2") (pinfunction "2_2") (pintype "passive"))
      (node (ref "R_PWRUSB") (pin "1") (pinfunction "1_1") (pintype "passive"))
      (node (ref "SJ1") (pin "1") (pinfunction "1_1") (pintype "passive"))
      (node (ref "TP4") (pin "TP") (pinfunction "TP_TP") (pintype "input"))
      (node (ref "TP5") (pin "TP") (pinfunction "TP_TP") (pintype "input"))
      (node (ref "U1") (pin "1") (pinfunction "GND_1") (pintype "power_in"))
      (node (ref "U1") (pin "28") (pinfunction "GND_28") (pintype "power_in"))
      (node (ref "U1") (pin "29_1") (pinfunction "GND_29_1") (pintype "power_in"))
      (node (ref "U1") (pin "29_2") (pinfunction "GND_29_2") (pintype "power_in"))
      (node (ref "U1") (pin "29_3") (pinfunction "GND_29_3") (pintype "power_in"))
      (node (ref "U1") (pin "29_4") (pinfunction "GND_29_4") (pintype "power_in"))
      (node (ref "U1") (pin "29_5") (pinfunction "GND_29_5") (pintype "power_in"))
      (node (ref "U1") (pin "29_6") (pinfunction "GND_29_6") (pintype "power_in"))
      (node (ref "U1") (pin "29_7") (pinfunction "GND_29_7") (pintype "power_in"))
      (node (ref "U1") (pin "29_8") (pinfunction "GND_29_8") (pintype "power_in"))
      (node (ref "U1") (pin "29_9") (pinfunction "GND_29_9") (pintype "power_in"))
      (node (ref "U2") (pin "1") (pinfunction "CTG_1") (pintype "power_in"))
      (node (ref "U2") (pin "4") (pinfunction "GND_4") (pintype "power_in"))
      (node (ref "U2") (pin "6") (pinfunction "QSTRT_6") (pintype "input"))
      (node (ref "U2") (pin "9") (pinfunction "EP_9") (pintype "power_in"))
      (node (ref "U3") (pin "13") (pinfunction "GND_13") (pintype "power_in"))
      (node (ref "U4") (pin "4") (pinfunction "GND_4") (pintype "power_in"))
      (node (ref "U4") (pin "9") (pinfunction "EXP_9") (pintype "passive"))
      (node (ref "U5") (pin "2") (pinfunction "VSS_2") (pintype "bidirectional"))
      (node (ref "U6") (pin "3") (pinfunction "GND_3") (pintype "bidirectional"))
      (node (ref "U7") (pin "2") (pinfunction "VSS_2") (pintype "power_in"))
      (node (ref "U8") (pin "1") (pinfunction "GND_1") (pintype "power_in"))
      (node (ref "U8") (pin "5") (pinfunction "SDO_5") (pintype "bidirectional"))
      (node (ref "U8") (pin "7") (pinfunction "GND_7") (pintype "power_in"))
    )
    (net (code "14") (name "GPIO8") (class "Default")
      (node (ref "R1") (pin "1") (pinfunction "1_1") (pintype "passive"))
      (node (ref "U1") (pin "10") (pinfunction "IO8_10") (pintype "bidirectional"))
    )
    (net (code "15") (name "I2C_PW") (class "Default")
      (node (ref "C1") (pin "1") (pinfunction "1_1") (pintype "passive"))
      (node (ref "C2") (pin "1") (pinfunction "1_1") (pintype "passive"))
      (node (ref "R1_PINH1") (pin "2") (pinfunction "2_2") (pintype "passive"))
      (node (ref "R2-PINH1") (pin "2") (pinfunction "2_2") (pintype "passive"))
      (node (ref "U1") (pin "17") (pinfunction "IO19_17") (pintype "bidirectional"))
      (node (ref "U8") (pin "2") (pinfunction "CSB_2") (pintype "input"))
      (node (ref "U8") (pin "6") (pinfunction "VDDIO_6") (pintype "power_in"))
      (node (ref "U8") (pin "8") (pinfunction "VDD_8") (pintype "power_in"))
    )
    (net (code "16") (name "INT_RTC") (class "Default")
      (node (ref "R1_PINH2") (pin "1") (pinfunction "1_1") (pintype "passive"))
      (node (ref "TP15") (pin "TP") (pinfunction "TP_TP") (pintype "input"))
      (node (ref "U1") (pin "8") (pinfunction "IO0_8") (pintype "bidirectional"))
      (node (ref "U3") (pin "3") (pinfunction "SQW/~{INT}_3") (pintype "output"))
    )
    (net (code "17") (name "IO{slash}BOOT") (class "Default")
      (node (ref "BOOT_BUTTON") (pin "3") (pinfunction "3_3") (pintype "passive"))
      (node (ref "BOOT_BUTTON") (pin "4") (pinfunction "4_4") (pintype "passive"))
      (node (ref "C5") (pin "1") (pinfunction "1_1") (pintype "passive"))
      (node (ref "R_BOOT") (pin "1") (pinfunction "1_1") (pintype "passive"))
      (node (ref "U1") (pin "15") (pinfunction "IO9_15") (pintype "bidirectional"))
    )
    (net (code "18") (name "IO{slash}CHANGE") (class "Default")
      (node (ref "C9") (pin "1") (pinfunction "1_1") (pintype "passive"))
      (node (ref "CHANGE_BUTTON") (pin "3") (pinfunction "3_3") (pintype "passive"))
      (node (ref "CHANGE_BUTTON") (pin "4") (pinfunction "4_4") (pintype "passive"))
      (node (ref "R_CHANGE") (pin "1") (pinfunction "1_1") (pintype "passive"))
      (node (ref "U1") (pin "23") (pinfunction "IO15_23") (pintype "bidirectional"))
    )
    (net (code "19") (name "MISO") (class "Default")
      (node (ref "D12") (pin "2") (pinfunction "2_2") (pintype "passive"))
      (node (ref "J4") (pin "P7") (pinfunction "DAT0_P7") (pintype "bidirectional"))
      (node (ref "R8") (pin "1") (pinfunction "1_1") (pintype "passive"))
      (node (ref "TP6") (pin "TP") (pinfunction "TP_TP") (pintype "input"))
      (node (ref "U1") (pin "27") (pinfunction "IO2_27") (pintype "bidirectional"))
      (node (ref "U4") (pin "2") (pinfunction "DO(IO1)_2") (pintype "bidirectional"))
    )
    (net (code "20") (name "MOSI") (class "Default")
      (node (ref "D11") (pin "2") (pinfunction "2_2") (pintype "passive"))
      (node (ref "J1") (pin "14") (pinfunction "14_14") (pintype "bidirectional"))
      (node (ref "J4") (pin "P3") (pinfunction "CMD_P3") (pintype "bidirectional"))
      (node (ref "R7") (pin "1") (pinfunction "1_1") (pintype "passive"))
      (node (ref "TP7") (pin "TP") (pinfunction "TP_TP") (pintype "input"))
      (node (ref "U1") (pin "7") (pinfunction "IO7_7") (pintype "bidirectional"))
      (node (ref "U4") (pin "5") (pinfunction "DI(IO0)_5") (pintype "bidirectional"))
    )
    (net (code "21") (name "Net-(CHG_LED-PadC)") (class "Default")
      (node (ref "CHG_LED") (pin "C") (pinfunction "C_C") (pintype "passive"))
      (node (ref "R1_BAT") (pin "1") (pinfunction "1_1") (pintype "passive"))
    )
    (net (code "22") (name "Net-(D2-CATHODE)") (class "Default")
      (node (ref "C1_BAT1") (pin "1") (pinfunction "1_1") (pintype "passive"))
      (node (ref "D2") (pin "1") (pinfunction "CATHODE_1") (pintype "bidirectional"))
      (node (ref "Q1") (pin "2") (pinfunction "S_2") (pintype "bidirectional"))
      (node (ref "U5") (pin "1") (pinfunction "VIN_1") (pintype "bidirectional"))
      (node (ref "U5") (pin "3") (pinfunction "CE_3") (pintype "bidirectional"))
    )
    (net (code "23") (name "Net-(D3-A)") (class "Default")
      (node (ref "C3") (pin "1") (pinfunction "1_1") (pintype "passive"))
      (node (ref "D3") (pin "2") (pinfunction "A_2") (pintype "bidirectional"))
      (node (ref "D4") (pin "1") (pinfunction "K_1") (pintype "bidirectional"))
    )
    (net (code "24") (name "Net-(D7-CATHODE)") (class "Default")
      (node (ref "D7") (pin "1") (pinfunction "CATHODE_1") (pintype "bidirectional"))
      (node (ref "R_CAPACITOR") (pin "1") (pinfunction "1_1") (pintype "passive"))
    )
    (net (code "25") (name "Net-(EPD_C1-Pad2)") (class "Default")
      (node (ref "EPD_C1") (pin "2") (pinfunction "2_2") (pintype "passive"))
      (node (ref "J1") (pin "4") (pinfunction "4_4") (pintype "bidirectional"))
    )
    (net (code "26") (name "Net-(EPD_C2-Pad2)") (class "Default")
      (node (ref "EPD_C2") (pin "2") (pinfunction "2_2") (pintype "passive"))
      (node (ref "J1") (pin "5") (pinfunction "5_5") (pintype "bidirectional"))
    )
    (net (code "27") (name "Net-(EPD_C4-Pad2)") (class "Default")
      (node (ref "EPD_C4") (pin "2") (pinfunction "2_2") (pintype "passive"))
      (node (ref "J1") (pin "18") (pinfunction "18_18") (pintype "bidirectional"))
    )
    (net (code "28") (name "Net-(EPD_C5-Pad2)") (class "Default")
      (node (ref "EPD_C5") (pin "2") (pinfunction "2_2") (pintype "passive"))
      (node (ref "J1") (pin "19") (pinfunction "19_19") (pintype "bidirectional"))
    )
    (net (code "29") (name "Net-(EPD_C6-Pad2)") (class "Default")
      (node (ref "EPD_C6") (pin "2") (pinfunction "2_2") (pintype "passive"))
      (node (ref "J1") (pin "20") (pinfunction "20_20") (pintype "bidirectional"))
    )
    (net (code "30") (name "Net-(EPD_C8-Pad2)") (class "Default")
      (node (ref "EPD_C8") (pin "2") (pinfunction "2_2") (pintype "passive"))
      (node (ref "J1") (pin "22") (pinfunction "22_22") (pintype "bidirectional"))
    )
    (net (code "31") (name "Net-(EPD_C10-Pad2)") (class "Default")
      (node (ref "EPD_C10") (pin "2") (pinfunction "2_2") (pintype "passive"))
      (node (ref "J1") (pin "24") (pinfunction "24_24") (pintype "bidirectional"))
    )
    (net (code "32") (name "Net-(J2-PadA5)") (class "Default")
      (node (ref "J2") (pin "A5") (pinfunction "A5_A5") (pintype "bidirectional"))
      (node (ref "R2_USB") (pin "2") (pinfunction "2_2") (pintype "passive"))
    )
    (net (code "33") (name "Net-(J2-PadB5)") (class "Default")
      (node (ref "J2") (pin "B5") (pinfunction "B5_B5") (pintype "bidirectional"))
      (node (ref "R1_USB") (pin "1") (pinfunction "1_1") (pintype "passive"))
    )
    (net (code "34") (name "Net-(U6-CT)") (class "Default")
      (node (ref "C_DELAY") (pin "1") (pinfunction "1_1") (pintype "passive"))
      (node (ref "U6") (pin "5") (pinfunction "CT_5") (pintype "bidirectional"))
    )
    (net (code "35") (name "Net-(U7-PROG)") (class "Default")
      (node (ref "R2_BAT") (pin "2") (pinfunction "2_2") (pintype "passive"))
      (node (ref "U7") (pin "5") (pinfunction "PROG_5") (pintype "input"))
    )
    (net (code "36") (name "Net-(U7-STAT)") (class "Default")
      (node (ref "R1_BAT") (pin "2") (pinfunction "2_2") (pintype "passive"))
      (node (ref "U7") (pin "1") (pinfunction "STAT_1") (pintype "output"))
    )
    (net (code "37") (name "PREVGH") (class "Default")
      (node (ref "D5") (pin "1") (pinfunction "K_1") (pintype "bidirectional"))
      (node (ref "EPD_C7") (pin "2") (pinfunction "2_2") (pintype "passive"))
      (node (ref "J1") (pin "21") (pinfunction "21_21") (pintype "bidirectional"))
    )
    (net (code "38") (name "PREVGL") (class "Default")
      (node (ref "D4") (pin "2") (pinfunction "A_2") (pintype "bidirectional"))
      (node (ref "EPD_C9") (pin "2") (pinfunction "2_2") (pintype "passive"))
      (node (ref "J1") (pin "23") (pinfunction "23_23") (pintype "bidirectional"))
    )
    (net (code "39") (name "RESE") (class "Default")
      (node (ref "J1") (pin "3") (pinfunction "3_3") (pintype "bidirectional"))
      (node (ref "Q3") (pin "2") (pinfunction "S_2") (pintype "bidirectional"))
      (node (ref "R3") (pin "2") (pinfunction "2_2") (pintype "passive"))
    )
    (net (code "40") (name "RESE'") (class "Default")
      (node (ref "R2") (pin "1") (pinfunction "1_1") (pintype "passive"))
      (node (ref "R3") (pin "1") (pinfunction "1_1") (pintype "passive"))
      (node (ref "SJ1") (pin "2") (pinfunction "2_2") (pintype "passive"))
    )
    (net (code "41") (name "RESET") (class "Default")
      (node (ref "C4") (pin "1") (pinfunction "1_1") (pintype "passive"))
      (node (ref "RESET_BUTTON") (pin "3") (pinfunction "3_3") (pintype "passive"))
      (node (ref "RESET_BUTTON") (pin "4") (pinfunction "4_4") (pintype "passive"))
      (node (ref "R_RESET") (pin "1") (pinfunction "1_1") (pintype "passive"))
      (node (ref "U1") (pin "3") (pinfunction "EN_3") (pintype "input"))
      (node (ref "U6") (pin "1") (pinfunction "VOUT_1") (pintype "bidirectional"))
    )
    (net (code "42") (name "RTC_RST") (class "Default")
      (node (ref "U1") (pin "16") (pinfunction "IO18_16") (pintype "bidirectional"))
      (node (ref "U3") (pin "4") (pinfunction "~{RST}_4") (pintype "input"))
    )
    (net (code "43") (name "RX") (class "Default")
      (node (ref "TP2") (pin "TP") (pinfunction "TP_TP") (pintype "input"))
      (node (ref "U1") (pin "24") (pinfunction "RXD0/GPIO17_24") (pintype "bidirectional"))
    )
    (net (code "44") (name "SCK") (class "Default")
      (node (ref "D10") (pin "2") (pinfunction "2_2") (pintype "passive"))
      (node (ref "J1") (pin "13") (pinfunction "13_13") (pintype "bidirectional"))
      (node (ref "J4") (pin "P5") (pinfunction "CLK_P5") (pintype "bidirectional"))
      (node (ref "R6") (pin "1") (pinfunction "1_1") (pintype "passive"))
      (node (ref "TP8") (pin "TP") (pinfunction "TP_TP") (pintype "input"))
      (node (ref "U1") (pin "6") (pinfunction "IO6_6") (pintype "bidirectional"))
      (node (ref "U4") (pin "6") (pinfunction "CLK_6") (pintype "input"))
    )
    (net (code "45") (name "SCL") (class "Default")
      (node (ref "J3") (pin "4") (pinfunction "4_4") (pintype "passive"))
      (node (ref "R2-PINH1") (pin "1") (pinfunction "1_1") (pintype "passive"))
      (node (ref "U1") (pin "20") (pinfunction "IO22_20") (pintype "bidirectional"))
      (node (ref "U2") (pin "7") (pinfunction "SCL_7") (pintype "input"))
      (node (ref "U3") (pin "16") (pinfunction "SCL_16") (pintype "input"))
      (node (ref "U8") (pin "4") (pinfunction "SCK_4") (pintype "input"))
    )
    (net (code "46") (name "SDA") (class "Default")
      (node (ref "J3") (pin "3") (pinfunction "3_3") (pintype "passive"))
      (node (ref "R1_PINH1") (pin "1") (pinfunction "1_1") (pintype "passive"))
      (node (ref "U1") (pin "19") (pinfunction "IO21_19") (pintype "bidirectional"))
      (node (ref "U2") (pin "8") (pinfunction "SDA_8") (pintype "bidirectional"))
      (node (ref "U3") (pin "15") (pinfunction "SDA_15") (pintype "bidirectional"))
      (node (ref "U8") (pin "3") (pinfunction "SDI_3") (pintype "bidirectional"))
    )
    (net (code "47") (name "SRC") (class "Default")
      (node (ref "C3") (pin "2") (pinfunction "2_2") (pintype "passive"))
      (node (ref "D5") (pin "2") (pinfunction "A_2") (pintype "bidirectional"))
      (node (ref "L1") (pin "1") (pinfunction "1_1") (pintype "passive"))
      (node (ref "Q3") (pin "3") (pinfunction "D_3") (pintype "bidirectional"))
    )
    (net (code "48") (name "SS_SD") (class "Default")
      (node (ref "D8") (pin "2") (pinfunction "2_2") (pintype "passive"))
      (node (ref "J4") (pin "P2") (pinfunction "CD/DAT3_P2") (pintype "bidirectional"))
      (node (ref "R10") (pin "1") (pinfunction "1_1") (pintype "passive"))
      (node (ref "U1") (pin "4") (pinfunction "IO4_4") (pintype "bidirectional"))
    )
    (net (code "49") (name "TX") (class "Default")
      (node (ref "TP1") (pin "TP") (pinfunction "TP_TP") (pintype "input"))
      (node (ref "U1") (pin "25") (pinfunction "TXD0/GPIO16_25") (pintype "bidirectional"))
    )
    (net (code "50") (name "USB_D+") (class "Default")
      (node (ref "D1") (pin "1") (pinfunction "I/O1_1_1") (pintype "bidirectional"))
      (node (ref "U1") (pin "14") (pinfunction "IO13_14") (pintype "bidirectional"))
    )
    (net (code "51") (name "USB_D-") (class "Default")
      (node (ref "D1") (pin "3") (pinfunction "I/O2_1_3") (pintype "bidirectional"))
      (node (ref "U1") (pin "13") (pinfunction "IO12_13") (pintype "bidirectional"))
    )
    (net (code "52") (name "VBAT") (class "Default")
      (node (ref "C2_BAT") (pin "1") (pinfunction "1_1") (pintype "passive"))
      (node (ref "Q1") (pin "3") (pinfunction "D_3") (pintype "bidirectional"))
      (node (ref "TP3") (pin "TP") (pinfunction "TP_TP") (pintype "input"))
      (node (ref "U2") (pin "2") (pinfunction "CELL_2") (pintype "power_in"))
      (node (ref "U2") (pin "3") (pinfunction "VDD_3") (pintype "power_in"))
      (node (ref "U7") (pin "3") (pinfunction "VBAT_3") (pintype "power_in"))
    )
    (net (code "53") (name "VBUS") (class "Default")
      (node (ref "C1_BAT") (pin "1") (pinfunction "1_1") (pintype "passive"))
      (node (ref "C3_USB") (pin "1") (pinfunction "1_1") (pintype "passive"))
      (node (ref "C4_USB") (pin "1") (pinfunction "1_1") (pintype "passive"))
      (node (ref "CHG_LED") (pin "A") (pinfunction "A_A") (pintype "passive"))
      (node (ref "D1") (pin "5") (pinfunction "VBUS_5") (pintype "bidirectional"))
      (node (ref "D2") (pin "2") (pinfunction "ANODE_2") (pintype "bidirectional"))
      (node (ref "PFMF.050.1") (pin "2") (pinfunction "2_2") (pintype "passive"))
      (node (ref "Q1") (pin "1") (pinfunction "G_1") (pintype "bidirectional"))
      (node (ref "R_PWRUSB") (pin "2") (pinfunction "2_2") (pintype "passive"))
      (node (ref "TP14") (pin "TP") (pinfunction "TP_TP") (pintype "input"))
      (node (ref "U7") (pin "4") (pinfunction "VIN_4") (pintype "power_in"))
    )
    (net (code "54") (name "VRTC") (class "Default")
      (node (ref "C7") (pin "1") (pinfunction "1_1") (pintype "passive"))
      (node (ref "C_SUPERCAP") (pin "2") (pinfunction "2_2") (pintype "passive"))
      (node (ref "R_CAPACITOR") (pin "2") (pinfunction "2_2") (pintype "passive"))
      (node (ref "U3") (pin "14") (pinfunction "VBAT_14") (pintype "power_in"))
    )
    (net (code "55") (name "VUSB") (class "Default")
      (node (ref "J2") (pin "A4") (pinfunction "A4_A4") (pintype "bidirectional"))
      (node (ref "J2") (pin "A9") (pinfunction "A9_A9") (pintype "bidirectional"))
      (node (ref "J2") (pin "B4") (pinfunction "B4_B4") (pintype "bidirectional"))
      (node (ref "J2") (pin "B9") (pinfunction "B9_B9") (pintype "bidirectional"))
      (node (ref "PFMF.050.1") (pin "1") (pinfunction "1_1") (pintype "passive"))
    )
    (net (code "56") (name "unconnected-(J1-Pad1)") (class "Default")
      (node (ref "J1") (pin "1") (pinfunction "1_1") (pintype "bidirectional"))
    )
    (net (code "57") (name "unconnected-(J1-Pad6)") (class "Default")
      (node (ref "J1") (pin "6") (pinfunction "6_6") (pintype "bidirectional"))
    )
    (net (code "58") (name "unconnected-(J1-Pad7)") (class "Default")
      (node (ref "J1") (pin "7") (pinfunction "7_7") (pintype "bidirectional"))
    )
    (net (code "59") (name "unconnected-(J2-PadA8)") (class "Default")
      (node (ref "J2") (pin "A8") (pinfunction "A8_A8") (pintype "bidirectional"))
    )
    (net (code "60") (name "unconnected-(J2-PadB8)") (class "Default")
      (node (ref "J2") (pin "B8") (pinfunction "B8_B8") (pintype "bidirectional"))
    )
    (net (code "61") (name "unconnected-(J4-DAT1-PadP8)") (class "Default")
      (node (ref "J4") (pin "P8") (pinfunction "DAT1_P8") (pintype "bidirectional"))
    )
    (net (code "62") (name "unconnected-(J4-DAT2-PadP1)") (class "Default")
      (node (ref "J4") (pin "P1") (pinfunction "DAT2_P1") (pintype "bidirectional"))
    )
    (net (code "63") (name "unconnected-(J4-DETECTION_1-PadS1)") (class "Default")
      (node (ref "J4") (pin "S1") (pinfunction "DETECTION_1_S1") (pintype "bidirectional"))
    )
    (net (code "64") (name "unconnected-(J4-DETECTION_2-PadS2)") (class "Default")
      (node (ref "J4") (pin "S2") (pinfunction "DETECTION_2_S2") (pintype "bidirectional"))
    )
    (net (code "65") (name "unconnected-(U1-NC-Pad22)") (class "Default")
      (node (ref "U1") (pin "22") (pinfunction "NC_22") (pintype "no_connect"))
    )
    (net (code "66") (name "unconnected-(U2-~{ALERT}-Pad5)") (class "Default")
      (node (ref "U2") (pin "5") (pinfunction "~{ALERT}_5") (pintype "output"))
    )
    (net (code "67") (name "unconnected-(U5-NC-Pad4)") (class "Default")
      (node (ref "U5") (pin "4") (pinfunction "NC_4") (pintype "no_connect"))
    )
    (net (code "68") (name "unconnected-(U6-NC-Pad4)") (class "Default")
      (node (ref "U6") (pin "4") (pinfunction "NC_4") (pintype "no_connect"))
    )
  )
)
